# Capstone.net
KiCad netlist of a schematic drawn in EAGLE
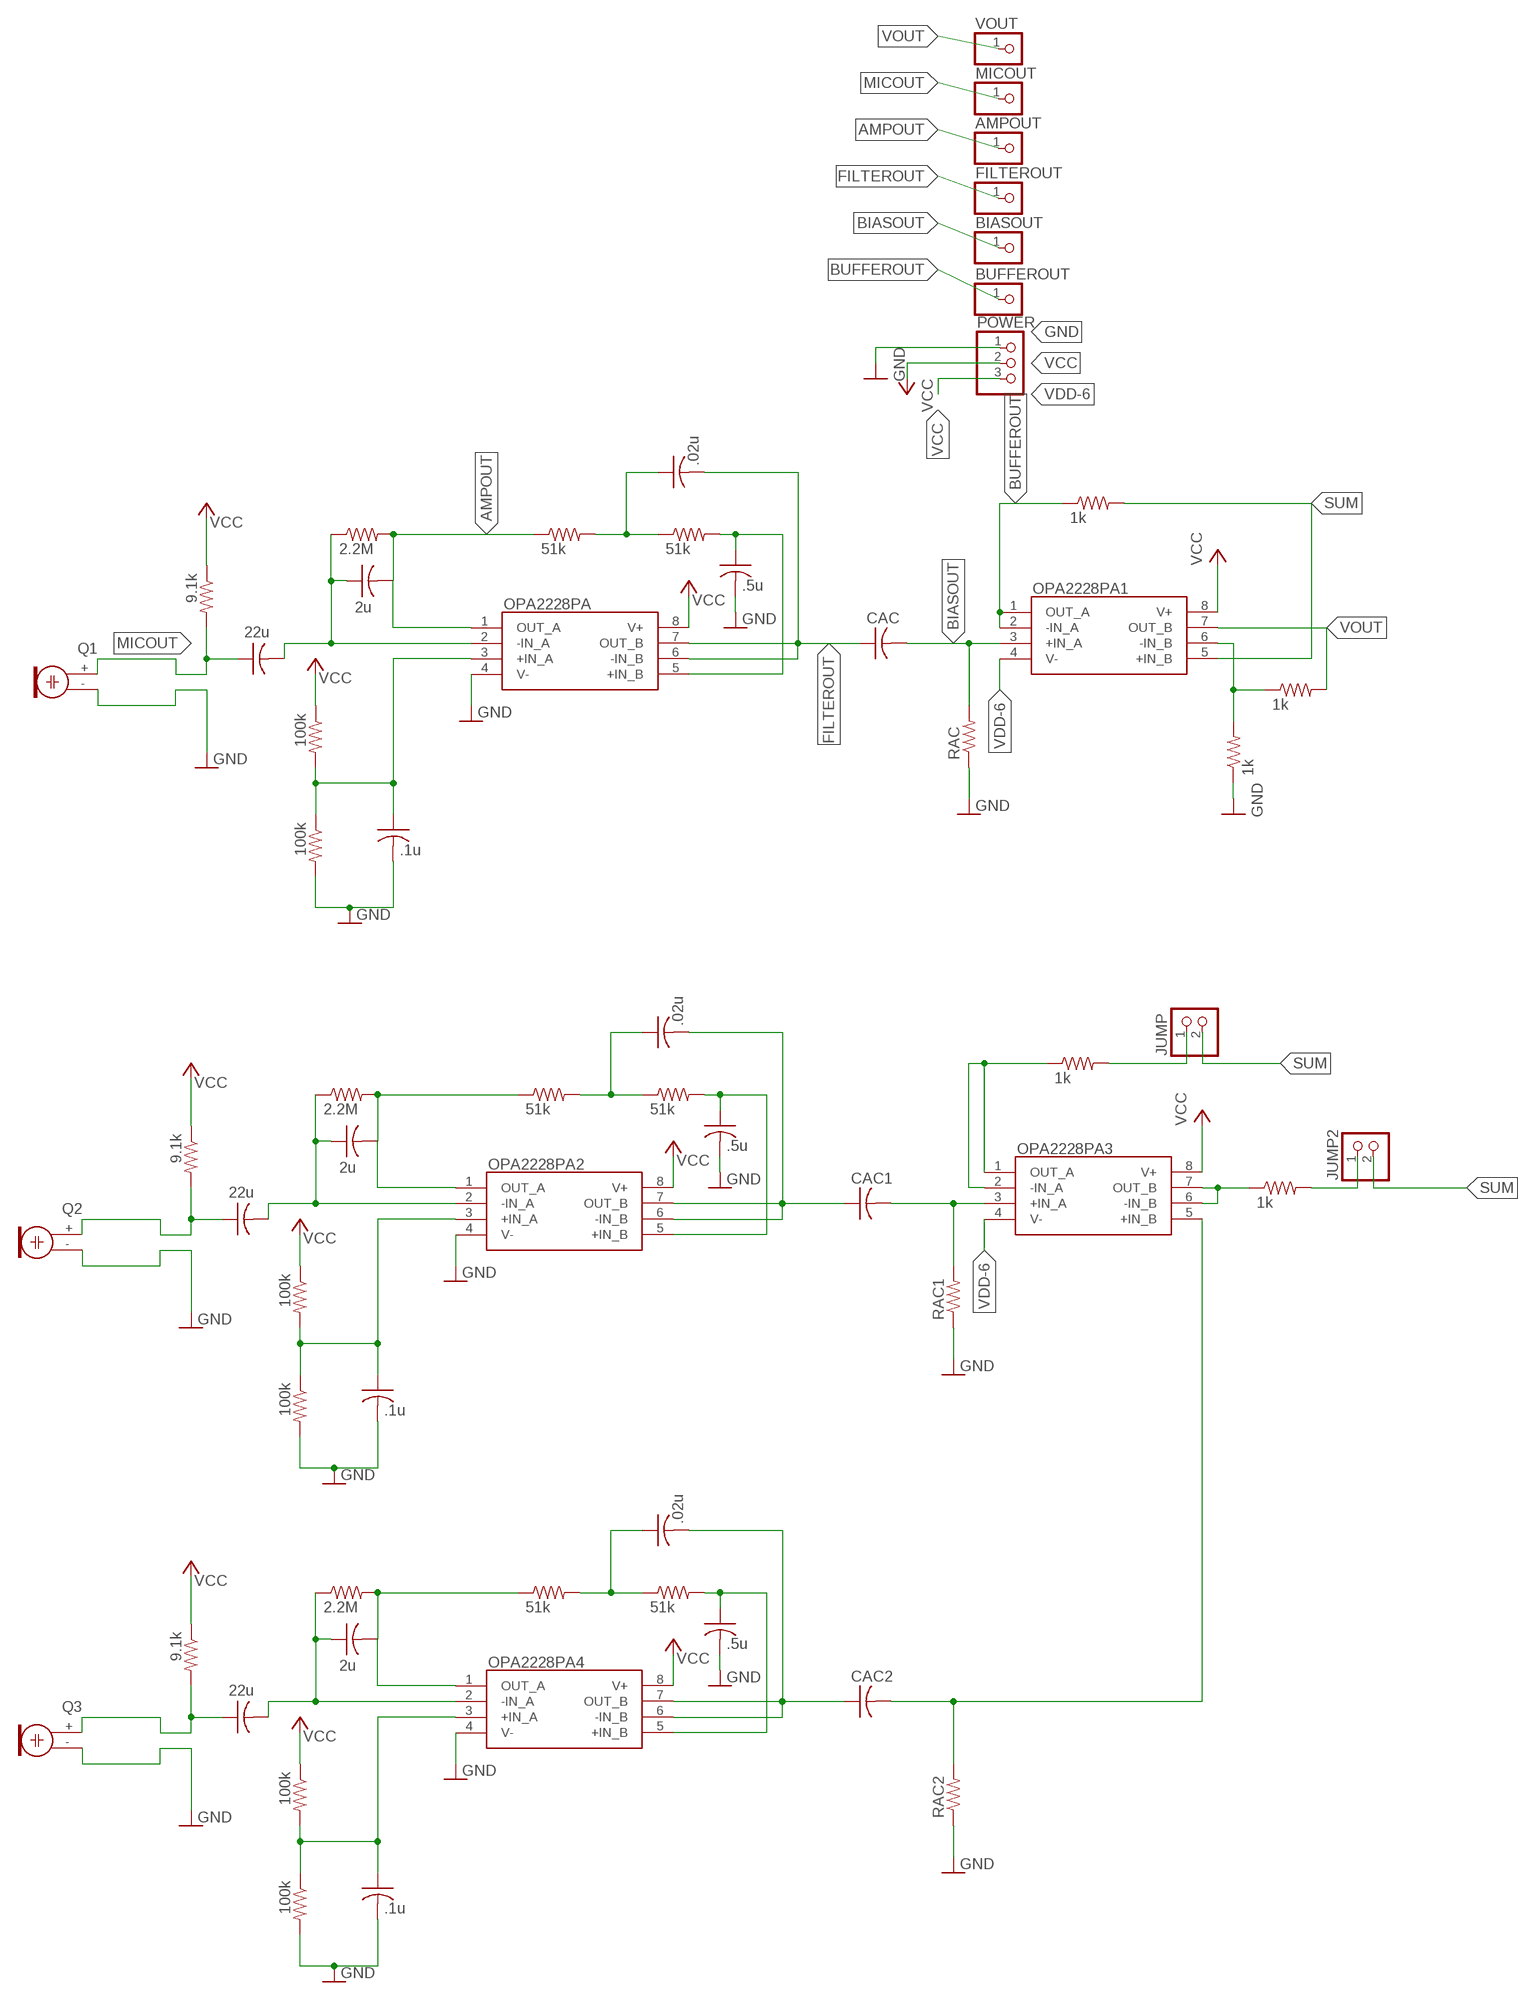
[diagram p0: schematic, sheet 1]

(export (version "E")
  (design (tool "Eeschema 10.0.6"))
  (components
    (comp (ref "AMPOUT")
      (value "PINHD-1X1")
      (footprint "eagle-import:1X01")
      (libsource (lib "eagle-import") (part "PINHD-1X1"))
    )
    (comp (ref "BIASOUT")
      (value "PINHD-1X1")
      (footprint "eagle-import:1X01")
      (libsource (lib "eagle-import") (part "PINHD-1X1"))
    )
    (comp (ref "BUFFEROUT")
      (value "PINHD-1X1")
      (footprint "eagle-import:1X01")
      (libsource (lib "eagle-import") (part "PINHD-1X1"))
    )
    (comp (ref "C1")
      (value ".1u")
      (footprint "eagle-import:C025-024X044")
      (libsource (lib "eagle-import") (part "C-US025-024X044"))
    )
    (comp (ref "C2")
      (value "2u")
      (footprint "eagle-import:C025-024X044")
      (libsource (lib "eagle-import") (part "C-US025-024X044"))
    )
    (comp (ref "C3")
      (value "22u")
      (footprint "eagle-import:C025-024X044")
      (libsource (lib "eagle-import") (part "C-US025-024X044"))
    )
    (comp (ref "C4")
      (value ".02u")
      (footprint "eagle-import:C025-024X044")
      (libsource (lib "eagle-import") (part "C-US025-024X044"))
    )
    (comp (ref "C5")
      (value ".5u")
      (footprint "eagle-import:C025-024X044")
      (libsource (lib "eagle-import") (part "C-US025-024X044"))
    )
    (comp (ref "C6")
      (value ".1u")
      (footprint "eagle-import:C025-024X044")
      (libsource (lib "eagle-import") (part "C-US025-024X044"))
    )
    (comp (ref "C7")
      (value "2u")
      (footprint "eagle-import:C025-024X044")
      (libsource (lib "eagle-import") (part "C-US025-024X044"))
    )
    (comp (ref "C8")
      (value "22u")
      (footprint "eagle-import:C025-024X044")
      (libsource (lib "eagle-import") (part "C-US025-024X044"))
    )
    (comp (ref "C9")
      (value ".02u")
      (footprint "eagle-import:C025-024X044")
      (libsource (lib "eagle-import") (part "C-US025-024X044"))
    )
    (comp (ref "C10")
      (value ".5u")
      (footprint "eagle-import:C025-024X044")
      (libsource (lib "eagle-import") (part "C-US025-024X044"))
    )
    (comp (ref "C11")
      (value ".1u")
      (footprint "eagle-import:C025-024X044")
      (libsource (lib "eagle-import") (part "C-US025-024X044"))
    )
    (comp (ref "C12")
      (value "2u")
      (footprint "eagle-import:C025-024X044")
      (libsource (lib "eagle-import") (part "C-US025-024X044"))
    )
    (comp (ref "C13")
      (value "22u")
      (footprint "eagle-import:C025-024X044")
      (libsource (lib "eagle-import") (part "C-US025-024X044"))
    )
    (comp (ref "C14")
      (value ".02u")
      (footprint "eagle-import:C025-024X044")
      (libsource (lib "eagle-import") (part "C-US025-024X044"))
    )
    (comp (ref "C15")
      (value ".5u")
      (footprint "eagle-import:C025-024X044")
      (libsource (lib "eagle-import") (part "C-US025-024X044"))
    )
    (comp (ref "CAC")
      (value "C-US025-024X044")
      (footprint "eagle-import:C025-024X044")
      (libsource (lib "eagle-import") (part "C-US025-024X044"))
    )
    (comp (ref "CAC1")
      (value "C-US025-024X044")
      (footprint "eagle-import:C025-024X044")
      (libsource (lib "eagle-import") (part "C-US025-024X044"))
    )
    (comp (ref "CAC2")
      (value "C-US025-024X044")
      (footprint "eagle-import:C025-024X044")
      (libsource (lib "eagle-import") (part "C-US025-024X044"))
    )
    (comp (ref "FILTEROUT")
      (value "PINHD-1X1")
      (footprint "eagle-import:1X01")
      (libsource (lib "eagle-import") (part "PINHD-1X1"))
    )
    (comp (ref "JUMP")
      (value "PINHD-1X2")
      (footprint "eagle-import:1X02")
      (libsource (lib "eagle-import") (part "PINHD-1X2"))
    )
    (comp (ref "JUMP2")
      (value "PINHD-1X2")
      (footprint "eagle-import:1X02")
      (libsource (lib "eagle-import") (part "PINHD-1X2"))
    )
    (comp (ref "MICOUT")
      (value "PINHD-1X1")
      (footprint "eagle-import:1X01")
      (libsource (lib "eagle-import") (part "PINHD-1X1"))
    )
    (comp (ref "OPA2228PA")
      (value "OPA2228PA")
      (footprint "eagle-import:DIP794W53P254L959H508Q8N")
      (fields (field (name "MOUSER_PART_NUMBER") "595-OPA2228PA"))
      (libsource (lib "eagle-import") (part "OPA2228PA"))
    )
    (comp (ref "OPA2228PA1")
      (value "OPA2228PA")
      (footprint "eagle-import:DIP794W53P254L959H508Q8N")
      (fields (field (name "MOUSER_PART_NUMBER") "595-OPA2228PA"))
      (libsource (lib "eagle-import") (part "OPA2228PA"))
    )
    (comp (ref "OPA2228PA2")
      (value "OPA2228PA")
      (footprint "eagle-import:DIP794W53P254L959H508Q8N")
      (fields (field (name "MOUSER_PART_NUMBER") "595-OPA2228PA"))
      (libsource (lib "eagle-import") (part "OPA2228PA"))
    )
    (comp (ref "OPA2228PA3")
      (value "OPA2228PA")
      (footprint "eagle-import:DIP794W53P254L959H508Q8N")
      (fields (field (name "MOUSER_PART_NUMBER") "595-OPA2228PA"))
      (libsource (lib "eagle-import") (part "OPA2228PA"))
    )
    (comp (ref "OPA2228PA4")
      (value "OPA2228PA")
      (footprint "eagle-import:DIP794W53P254L959H508Q8N")
      (fields (field (name "MOUSER_PART_NUMBER") "595-OPA2228PA"))
      (libsource (lib "eagle-import") (part "OPA2228PA"))
    )
    (comp (ref "POWER")
      (value "PINHD-1X3")
      (footprint "eagle-import:1X03")
      (libsource (lib "eagle-import") (part "PINHD-1X3"))
    )
    (comp (ref "Q1")
      (value "ELECTRET")
      (footprint "eagle-import:9.7ELECTRET")
      (libsource (lib "eagle-import") (part "ELECTRET"))
    )
    (comp (ref "Q2")
      (value "ELECTRET")
      (footprint "eagle-import:9.7ELECTRET")
      (libsource (lib "eagle-import") (part "ELECTRET"))
    )
    (comp (ref "Q3")
      (value "ELECTRET")
      (footprint "eagle-import:9.7ELECTRET")
      (libsource (lib "eagle-import") (part "ELECTRET"))
    )
    (comp (ref "R1")
      (value "9.1k")
      (footprint "eagle-import:0204_7")
      (libsource (lib "eagle-import") (part "R-US_0204/7"))
    )
    (comp (ref "R2")
      (value "100k")
      (footprint "eagle-import:0204_7")
      (libsource (lib "eagle-import") (part "R-US_0204/7"))
    )
    (comp (ref "R3")
      (value "100k")
      (footprint "eagle-import:0204_7")
      (libsource (lib "eagle-import") (part "R-US_0204/7"))
    )
    (comp (ref "R4")
      (value "2.2M")
      (footprint "eagle-import:0204_7")
      (libsource (lib "eagle-import") (part "R-US_0204/7"))
    )
    (comp (ref "R5")
      (value "51k")
      (footprint "eagle-import:0204_7")
      (libsource (lib "eagle-import") (part "R-US_0204/7"))
    )
    (comp (ref "R6")
      (value "51k")
      (footprint "eagle-import:0204_7")
      (libsource (lib "eagle-import") (part "R-US_0204/7"))
    )
    (comp (ref "R7")
      (value "1k")
      (footprint "eagle-import:0204_7")
      (libsource (lib "eagle-import") (part "R-US_0204/7"))
    )
    (comp (ref "R8")
      (value "1k")
      (footprint "eagle-import:0204_7")
      (libsource (lib "eagle-import") (part "R-US_0204/7"))
    )
    (comp (ref "R9")
      (value "1k")
      (footprint "eagle-import:0204_7")
      (libsource (lib "eagle-import") (part "R-US_0204/7"))
    )
    (comp (ref "R10")
      (value "9.1k")
      (footprint "eagle-import:0204_7")
      (libsource (lib "eagle-import") (part "R-US_0204/7"))
    )
    (comp (ref "R11")
      (value "100k")
      (footprint "eagle-import:0204_7")
      (libsource (lib "eagle-import") (part "R-US_0204/7"))
    )
    (comp (ref "R12")
      (value "100k")
      (footprint "eagle-import:0204_7")
      (libsource (lib "eagle-import") (part "R-US_0204/7"))
    )
    (comp (ref "R13")
      (value "2.2M")
      (footprint "eagle-import:0204_7")
      (libsource (lib "eagle-import") (part "R-US_0204/7"))
    )
    (comp (ref "R14")
      (value "51k")
      (footprint "eagle-import:0204_7")
      (libsource (lib "eagle-import") (part "R-US_0204/7"))
    )
    (comp (ref "R15")
      (value "51k")
      (footprint "eagle-import:0204_7")
      (libsource (lib "eagle-import") (part "R-US_0204/7"))
    )
    (comp (ref "R16")
      (value "1k")
      (footprint "eagle-import:0204_7")
      (libsource (lib "eagle-import") (part "R-US_0204/7"))
    )
    (comp (ref "R17")
      (value "9.1k")
      (footprint "eagle-import:0204_7")
      (libsource (lib "eagle-import") (part "R-US_0204/7"))
    )
    (comp (ref "R18")
      (value "100k")
      (footprint "eagle-import:0204_7")
      (libsource (lib "eagle-import") (part "R-US_0204/7"))
    )
    (comp (ref "R19")
      (value "100k")
      (footprint "eagle-import:0204_7")
      (libsource (lib "eagle-import") (part "R-US_0204/7"))
    )
    (comp (ref "R20")
      (value "2.2M")
      (footprint "eagle-import:0204_7")
      (libsource (lib "eagle-import") (part "R-US_0204/7"))
    )
    (comp (ref "R21")
      (value "51k")
      (footprint "eagle-import:0204_7")
      (libsource (lib "eagle-import") (part "R-US_0204/7"))
    )
    (comp (ref "R22")
      (value "51k")
      (footprint "eagle-import:0204_7")
      (libsource (lib "eagle-import") (part "R-US_0204/7"))
    )
    (comp (ref "R23")
      (value "1k")
      (footprint "eagle-import:0204_7")
      (libsource (lib "eagle-import") (part "R-US_0204/7"))
    )
    (comp (ref "RAC")
      (value "R-US_0204/7")
      (footprint "eagle-import:0204_7")
      (libsource (lib "eagle-import") (part "R-US_0204/7"))
    )
    (comp (ref "RAC1")
      (value "R-US_0204/7")
      (footprint "eagle-import:0204_7")
      (libsource (lib "eagle-import") (part "R-US_0204/7"))
    )
    (comp (ref "RAC2")
      (value "R-US_0204/7")
      (footprint "eagle-import:0204_7")
      (libsource (lib "eagle-import") (part "R-US_0204/7"))
    )
    (comp (ref "VOUT")
      (value "PINHD-1X1")
      (footprint "eagle-import:1X01")
      (libsource (lib "eagle-import") (part "PINHD-1X1"))
    )
  )
  (nets
    (net (code "1") (name "AMPOUT") (class "Default")
      (node (ref "AMPOUT") (pin "1") (pinfunction "1_1") (pintype "passive"))
      (node (ref "C2") (pin "2") (pinfunction "2_2") (pintype "passive"))
      (node (ref "OPA2228PA") (pin "1") (pinfunction "OUT_A_1") (pintype "bidirectional"))
      (node (ref "R4") (pin "2") (pinfunction "2_2") (pintype "passive"))
      (node (ref "R5") (pin "1") (pinfunction "1_1") (pintype "passive"))
    )
    (net (code "2") (name "BIASOUT") (class "Default")
      (node (ref "BIASOUT") (pin "1") (pinfunction "1_1") (pintype "passive"))
      (node (ref "CAC") (pin "2") (pinfunction "2_2") (pintype "passive"))
      (node (ref "OPA2228PA1") (pin "3") (pinfunction "+IN_A_3") (pintype "bidirectional"))
      (node (ref "RAC") (pin "2") (pinfunction "2_2") (pintype "passive"))
    )
    (net (code "3") (name "BUFFEROUT") (class "Default")
      (node (ref "BUFFEROUT") (pin "1") (pinfunction "1_1") (pintype "passive"))
      (node (ref "OPA2228PA1") (pin "1") (pinfunction "OUT_A_1") (pintype "bidirectional"))
      (node (ref "OPA2228PA1") (pin "2") (pinfunction "-IN_A_2") (pintype "bidirectional"))
      (node (ref "R8") (pin "1") (pinfunction "1_1") (pintype "passive"))
    )
    (net (code "4") (name "FILTEROUT") (class "Default")
      (node (ref "C4") (pin "2") (pinfunction "2_2") (pintype "passive"))
      (node (ref "CAC") (pin "1") (pinfunction "1_1") (pintype "passive"))
      (node (ref "FILTEROUT") (pin "1") (pinfunction "1_1") (pintype "passive"))
      (node (ref "OPA2228PA") (pin "6") (pinfunction "-IN_B_6") (pintype "bidirectional"))
      (node (ref "OPA2228PA") (pin "7") (pinfunction "OUT_B_7") (pintype "bidirectional"))
    )
    (net (code "5") (name "GND") (class "Default")
      (node (ref "C1") (pin "2") (pinfunction "2_2") (pintype "passive"))
      (node (ref "C10") (pin "2") (pinfunction "2_2") (pintype "passive"))
      (node (ref "C11") (pin "2") (pinfunction "2_2") (pintype "passive"))
      (node (ref "C15") (pin "2") (pinfunction "2_2") (pintype "passive"))
      (node (ref "C5") (pin "2") (pinfunction "2_2") (pintype "passive"))
      (node (ref "C6") (pin "2") (pinfunction "2_2") (pintype "passive"))
      (node (ref "OPA2228PA") (pin "4") (pinfunction "V-_4") (pintype "bidirectional"))
      (node (ref "OPA2228PA2") (pin "4") (pinfunction "V-_4") (pintype "bidirectional"))
      (node (ref "OPA2228PA4") (pin "4") (pinfunction "V-_4") (pintype "bidirectional"))
      (node (ref "POWER") (pin "1") (pinfunction "1_1") (pintype "passive"))
      (node (ref "Q1") (pin "-") (pinfunction "1_-") (pintype "passive"))
      (node (ref "Q2") (pin "-") (pinfunction "1_-") (pintype "passive"))
      (node (ref "Q3") (pin "-") (pinfunction "1_-") (pintype "passive"))
      (node (ref "R12") (pin "2") (pinfunction "2_2") (pintype "passive"))
      (node (ref "R19") (pin "2") (pinfunction "2_2") (pintype "passive"))
      (node (ref "R3") (pin "2") (pinfunction "2_2") (pintype "passive"))
      (node (ref "R7") (pin "1") (pinfunction "1_1") (pintype "passive"))
      (node (ref "RAC") (pin "1") (pinfunction "1_1") (pintype "passive"))
      (node (ref "RAC1") (pin "1") (pinfunction "1_1") (pintype "passive"))
      (node (ref "RAC2") (pin "1") (pinfunction "1_1") (pintype "passive"))
    )
    (net (code "6") (name "MICOUT") (class "Default")
      (node (ref "C3") (pin "1") (pinfunction "1_1") (pintype "passive"))
      (node (ref "MICOUT") (pin "1") (pinfunction "1_1") (pintype "passive"))
      (node (ref "Q1") (pin "+") (pinfunction "2_+") (pintype "passive"))
      (node (ref "R1") (pin "2") (pinfunction "2_2") (pintype "passive"))
    )
    (net (code "7") (name "Net-(C4-Pad1)") (class "Default")
      (node (ref "C4") (pin "1") (pinfunction "1_1") (pintype "passive"))
      (node (ref "R5") (pin "2") (pinfunction "2_2") (pintype "passive"))
      (node (ref "R6") (pin "1") (pinfunction "1_1") (pintype "passive"))
    )
    (net (code "8") (name "Net-(C9-Pad1)") (class "Default")
      (node (ref "C9") (pin "1") (pinfunction "1_1") (pintype "passive"))
      (node (ref "R14") (pin "2") (pinfunction "2_2") (pintype "passive"))
      (node (ref "R15") (pin "1") (pinfunction "1_1") (pintype "passive"))
    )
    (net (code "9") (name "Net-(C14-Pad1)") (class "Default")
      (node (ref "C14") (pin "1") (pinfunction "1_1") (pintype "passive"))
      (node (ref "R21") (pin "2") (pinfunction "2_2") (pintype "passive"))
      (node (ref "R22") (pin "1") (pinfunction "1_1") (pintype "passive"))
    )
    (net (code "10") (name "Net-(JUMP-Pad1)") (class "Default")
      (node (ref "JUMP") (pin "1") (pinfunction "1_1") (pintype "passive"))
      (node (ref "R16") (pin "2") (pinfunction "2_2") (pintype "passive"))
    )
    (net (code "11") (name "Net-(JUMP2-Pad1)") (class "Default")
      (node (ref "JUMP2") (pin "1") (pinfunction "1_1") (pintype "passive"))
      (node (ref "R23") (pin "2") (pinfunction "2_2") (pintype "passive"))
    )
    (net (code "12") (name "Net-(OPA2228PA-+IN_A)") (class "Default")
      (node (ref "C1") (pin "1") (pinfunction "1_1") (pintype "passive"))
      (node (ref "OPA2228PA") (pin "3") (pinfunction "+IN_A_3") (pintype "bidirectional"))
      (node (ref "R2") (pin "2") (pinfunction "2_2") (pintype "passive"))
      (node (ref "R3") (pin "1") (pinfunction "1_1") (pintype "passive"))
    )
    (net (code "13") (name "Net-(OPA2228PA-+IN_B)") (class "Default")
      (node (ref "C5") (pin "1") (pinfunction "1_1") (pintype "passive"))
      (node (ref "OPA2228PA") (pin "5") (pinfunction "+IN_B_5") (pintype "bidirectional"))
      (node (ref "R6") (pin "2") (pinfunction "2_2") (pintype "passive"))
    )
    (net (code "14") (name "Net-(OPA2228PA--IN_A)") (class "Default")
      (node (ref "C2") (pin "1") (pinfunction "1_1") (pintype "passive"))
      (node (ref "C3") (pin "2") (pinfunction "2_2") (pintype "passive"))
      (node (ref "OPA2228PA") (pin "2") (pinfunction "-IN_A_2") (pintype "bidirectional"))
      (node (ref "R4") (pin "1") (pinfunction "1_1") (pintype "passive"))
    )
    (net (code "15") (name "Net-(OPA2228PA1--IN_B)") (class "Default")
      (node (ref "OPA2228PA1") (pin "6") (pinfunction "-IN_B_6") (pintype "bidirectional"))
      (node (ref "R7") (pin "2") (pinfunction "2_2") (pintype "passive"))
      (node (ref "R9") (pin "1") (pinfunction "1_1") (pintype "passive"))
    )
    (net (code "16") (name "Net-(OPA2228PA2-+IN_A)") (class "Default")
      (node (ref "C6") (pin "1") (pinfunction "1_1") (pintype "passive"))
      (node (ref "OPA2228PA2") (pin "3") (pinfunction "+IN_A_3") (pintype "bidirectional"))
      (node (ref "R11") (pin "2") (pinfunction "2_2") (pintype "passive"))
      (node (ref "R12") (pin "1") (pinfunction "1_1") (pintype "passive"))
    )
    (net (code "17") (name "Net-(OPA2228PA2-+IN_B)") (class "Default")
      (node (ref "C10") (pin "1") (pinfunction "1_1") (pintype "passive"))
      (node (ref "OPA2228PA2") (pin "5") (pinfunction "+IN_B_5") (pintype "bidirectional"))
      (node (ref "R15") (pin "2") (pinfunction "2_2") (pintype "passive"))
    )
    (net (code "18") (name "Net-(OPA2228PA2--IN_A)") (class "Default")
      (node (ref "C7") (pin "1") (pinfunction "1_1") (pintype "passive"))
      (node (ref "C8") (pin "2") (pinfunction "2_2") (pintype "passive"))
      (node (ref "OPA2228PA2") (pin "2") (pinfunction "-IN_A_2") (pintype "bidirectional"))
      (node (ref "R13") (pin "1") (pinfunction "1_1") (pintype "passive"))
    )
    (net (code "19") (name "Net-(OPA2228PA2--IN_B)") (class "Default")
      (node (ref "C9") (pin "2") (pinfunction "2_2") (pintype "passive"))
      (node (ref "CAC1") (pin "1") (pinfunction "1_1") (pintype "passive"))
      (node (ref "OPA2228PA2") (pin "6") (pinfunction "-IN_B_6") (pintype "bidirectional"))
      (node (ref "OPA2228PA2") (pin "7") (pinfunction "OUT_B_7") (pintype "bidirectional"))
    )
    (net (code "20") (name "Net-(OPA2228PA2-OUT_A)") (class "Default")
      (node (ref "C7") (pin "2") (pinfunction "2_2") (pintype "passive"))
      (node (ref "OPA2228PA2") (pin "1") (pinfunction "OUT_A_1") (pintype "bidirectional"))
      (node (ref "R13") (pin "2") (pinfunction "2_2") (pintype "passive"))
      (node (ref "R14") (pin "1") (pinfunction "1_1") (pintype "passive"))
    )
    (net (code "21") (name "Net-(OPA2228PA3-+IN_A)") (class "Default")
      (node (ref "CAC1") (pin "2") (pinfunction "2_2") (pintype "passive"))
      (node (ref "OPA2228PA3") (pin "3") (pinfunction "+IN_A_3") (pintype "bidirectional"))
      (node (ref "RAC1") (pin "2") (pinfunction "2_2") (pintype "passive"))
    )
    (net (code "22") (name "Net-(OPA2228PA3-+IN_B)") (class "Default")
      (node (ref "CAC2") (pin "2") (pinfunction "2_2") (pintype "passive"))
      (node (ref "OPA2228PA3") (pin "5") (pinfunction "+IN_B_5") (pintype "bidirectional"))
      (node (ref "RAC2") (pin "2") (pinfunction "2_2") (pintype "passive"))
    )
    (net (code "23") (name "Net-(OPA2228PA3--IN_A)") (class "Default")
      (node (ref "OPA2228PA3") (pin "1") (pinfunction "OUT_A_1") (pintype "bidirectional"))
      (node (ref "OPA2228PA3") (pin "2") (pinfunction "-IN_A_2") (pintype "bidirectional"))
      (node (ref "R16") (pin "1") (pinfunction "1_1") (pintype "passive"))
    )
    (net (code "24") (name "Net-(OPA2228PA3--IN_B)") (class "Default")
      (node (ref "OPA2228PA3") (pin "6") (pinfunction "-IN_B_6") (pintype "bidirectional"))
      (node (ref "OPA2228PA3") (pin "7") (pinfunction "OUT_B_7") (pintype "bidirectional"))
      (node (ref "R23") (pin "1") (pinfunction "1_1") (pintype "passive"))
    )
    (net (code "25") (name "Net-(OPA2228PA4-+IN_A)") (class "Default")
      (node (ref "C11") (pin "1") (pinfunction "1_1") (pintype "passive"))
      (node (ref "OPA2228PA4") (pin "3") (pinfunction "+IN_A_3") (pintype "bidirectional"))
      (node (ref "R18") (pin "2") (pinfunction "2_2") (pintype "passive"))
      (node (ref "R19") (pin "1") (pinfunction "1_1") (pintype "passive"))
    )
    (net (code "26") (name "Net-(OPA2228PA4-+IN_B)") (class "Default")
      (node (ref "C15") (pin "1") (pinfunction "1_1") (pintype "passive"))
      (node (ref "OPA2228PA4") (pin "5") (pinfunction "+IN_B_5") (pintype "bidirectional"))
      (node (ref "R22") (pin "2") (pinfunction "2_2") (pintype "passive"))
    )
    (net (code "27") (name "Net-(OPA2228PA4--IN_A)") (class "Default")
      (node (ref "C12") (pin "1") (pinfunction "1_1") (pintype "passive"))
      (node (ref "C13") (pin "2") (pinfunction "2_2") (pintype "passive"))
      (node (ref "OPA2228PA4") (pin "2") (pinfunction "-IN_A_2") (pintype "bidirectional"))
      (node (ref "R20") (pin "1") (pinfunction "1_1") (pintype "passive"))
    )
    (net (code "28") (name "Net-(OPA2228PA4--IN_B)") (class "Default")
      (node (ref "C14") (pin "2") (pinfunction "2_2") (pintype "passive"))
      (node (ref "CAC2") (pin "1") (pinfunction "1_1") (pintype "passive"))
      (node (ref "OPA2228PA4") (pin "6") (pinfunction "-IN_B_6") (pintype "bidirectional"))
      (node (ref "OPA2228PA4") (pin "7") (pinfunction "OUT_B_7") (pintype "bidirectional"))
    )
    (net (code "29") (name "Net-(OPA2228PA4-OUT_A)") (class "Default")
      (node (ref "C12") (pin "2") (pinfunction "2_2") (pintype "passive"))
      (node (ref "OPA2228PA4") (pin "1") (pinfunction "OUT_A_1") (pintype "bidirectional"))
      (node (ref "R20") (pin "2") (pinfunction "2_2") (pintype "passive"))
      (node (ref "R21") (pin "1") (pinfunction "1_1") (pintype "passive"))
    )
    (net (code "30") (name "Net-(Q2-2)") (class "Default")
      (node (ref "C8") (pin "1") (pinfunction "1_1") (pintype "passive"))
      (node (ref "Q2") (pin "+") (pinfunction "2_+") (pintype "passive"))
      (node (ref "R10") (pin "2") (pinfunction "2_2") (pintype "passive"))
    )
    (net (code "31") (name "Net-(Q3-2)") (class "Default")
      (node (ref "C13") (pin "1") (pinfunction "1_1") (pintype "passive"))
      (node (ref "Q3") (pin "+") (pinfunction "2_+") (pintype "passive"))
      (node (ref "R17") (pin "2") (pinfunction "2_2") (pintype "passive"))
    )
    (net (code "32") (name "SUM") (class "Default")
      (node (ref "JUMP") (pin "2") (pinfunction "2_2") (pintype "passive"))
      (node (ref "JUMP2") (pin "2") (pinfunction "2_2") (pintype "passive"))
      (node (ref "OPA2228PA1") (pin "5") (pinfunction "+IN_B_5") (pintype "bidirectional"))
      (node (ref "R8") (pin "2") (pinfunction "2_2") (pintype "passive"))
    )
    (net (code "33") (name "VCC") (class "Default")
      (node (ref "OPA2228PA") (pin "8") (pinfunction "V+_8") (pintype "bidirectional"))
      (node (ref "OPA2228PA1") (pin "8") (pinfunction "V+_8") (pintype "bidirectional"))
      (node (ref "OPA2228PA2") (pin "8") (pinfunction "V+_8") (pintype "bidirectional"))
      (node (ref "OPA2228PA3") (pin "8") (pinfunction "V+_8") (pintype "bidirectional"))
      (node (ref "OPA2228PA4") (pin "8") (pinfunction "V+_8") (pintype "bidirectional"))
      (node (ref "POWER") (pin "2") (pinfunction "2_2") (pintype "passive"))
      (node (ref "R1") (pin "1") (pinfunction "1_1") (pintype "passive"))
      (node (ref "R10") (pin "1") (pinfunction "1_1") (pintype "passive"))
      (node (ref "R11") (pin "1") (pinfunction "1_1") (pintype "passive"))
      (node (ref "R17") (pin "1") (pinfunction "1_1") (pintype "passive"))
      (node (ref "R18") (pin "1") (pinfunction "1_1") (pintype "passive"))
      (node (ref "R2") (pin "1") (pinfunction "1_1") (pintype "passive"))
    )
    (net (code "34") (name "VDD-6") (class "Default")
      (node (ref "OPA2228PA1") (pin "4") (pinfunction "V-_4") (pintype "bidirectional"))
      (node (ref "OPA2228PA3") (pin "4") (pinfunction "V-_4") (pintype "bidirectional"))
      (node (ref "POWER") (pin "3") (pinfunction "3_3") (pintype "passive"))
    )
    (net (code "35") (name "VOUT") (class "Default")
      (node (ref "OPA2228PA1") (pin "7") (pinfunction "OUT_B_7") (pintype "bidirectional"))
      (node (ref "R9") (pin "2") (pinfunction "2_2") (pintype "passive"))
      (node (ref "VOUT") (pin "1") (pinfunction "1_1") (pintype "passive"))
    )
  )
)
